# china_mp3_board.net
KiCad netlist of a schematic drawn in EAGLE
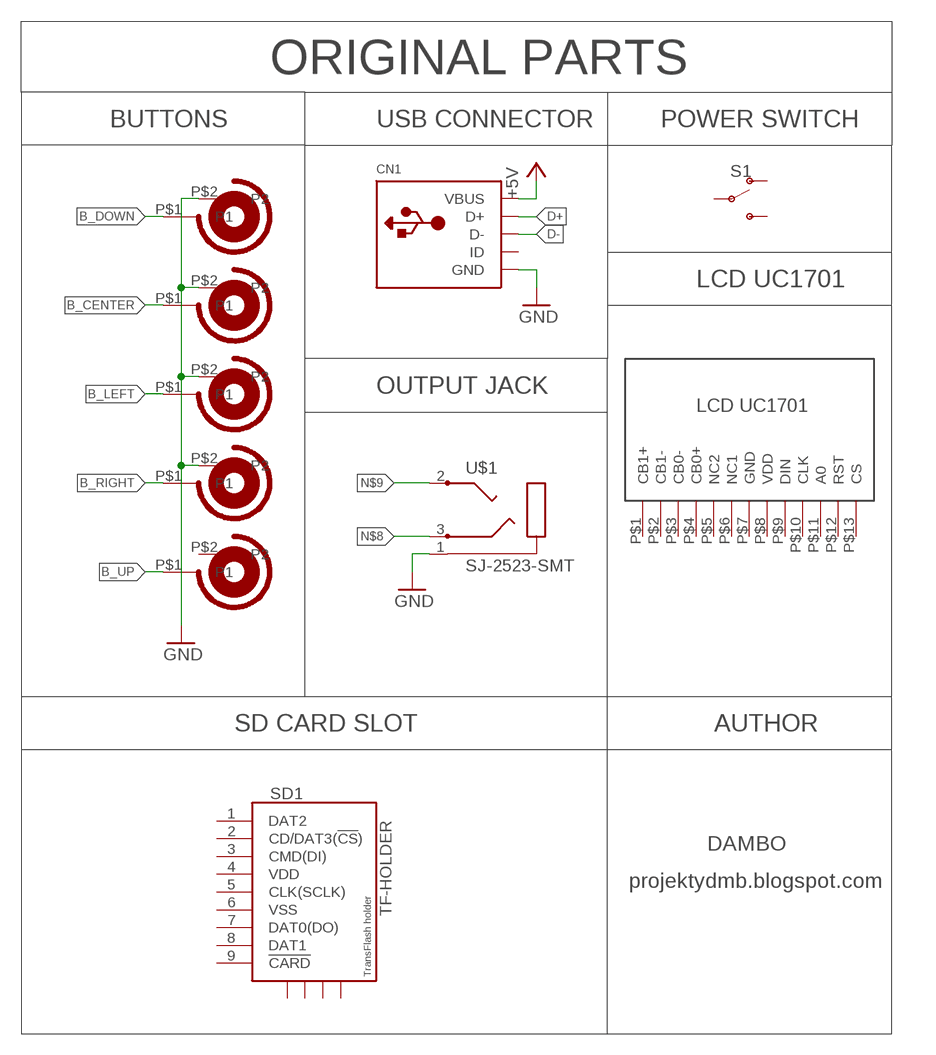
[diagram p0: schematic, sheet 1]

(export (version "E")
  (design (tool "Eeschema 10.0.6"))
  (components
    (comp (ref "CN1")
      (value "USBMINIB")
      (footprint "eagle-import:USB-MINIB")
      (libsource (lib "eagle-import") (part "USBMINIB"))
    )
    (comp (ref "S1")
      (value "SWITCH-SPDT-SMD-RIGHT-ANGLE")
      (footprint "eagle-import:SWITCH_SPST_SMD_A")
      (libsource (lib "eagle-import") (part "SWITCH-SPDT-SMD-RIGHT-ANGLE"))
    )
    (comp (ref "SD1")
      (value "TF-HOLDER")
      (footprint "eagle-import:TF-PULL")
      (libsource (lib "eagle-import") (part "TF-HOLDER"))
    )
    (comp (ref "U$1")
      (value "SJ-2523-SMT")
      (footprint "eagle-import:SJ-2523-SMT")
      (libsource (lib "eagle-import") (part "SJ-2523-SMT"))
    )
    (comp (ref "U$2")
      (value "BUTTON_TACT")
      (footprint "eagle-import:BUTTON_TACT_PACKAGE")
      (libsource (lib "eagle-import") (part "BUTTON_TACT"))
    )
    (comp (ref "U$3")
      (value "BUTTON_TACT")
      (footprint "eagle-import:BUTTON_TACT_PACKAGE")
      (libsource (lib "eagle-import") (part "BUTTON_TACT"))
    )
    (comp (ref "U$4")
      (value "BUTTON_TACT")
      (footprint "eagle-import:BUTTON_TACT_PACKAGE")
      (libsource (lib "eagle-import") (part "BUTTON_TACT"))
    )
    (comp (ref "U$5")
      (value "BUTTON_TACT")
      (footprint "eagle-import:BUTTON_TACT_PACKAGE")
      (libsource (lib "eagle-import") (part "BUTTON_TACT"))
    )
    (comp (ref "U$6")
      (value "BUTTON_TACT")
      (footprint "eagle-import:BUTTON_TACT_PACKAGE")
      (libsource (lib "eagle-import") (part "BUTTON_TACT"))
    )
    (comp (ref "U$7")
      (value "CHINA_MP3_LCD")
      (footprint "eagle-import:ONLY_PINS")
      (libsource (lib "eagle-import") (part "CHINA_MP3_LCD"))
    )
  )
  (nets
    (net (code "1") (name "+5V") (class "Default")
      (node (ref "CN1") (pin "VBUS") (pinfunction "VBUS_VBUS") (pintype "power_in"))
    )
    (net (code "2") (name "/VDD") (class "Default")
      (node (ref "SD1") (pin "4") (pinfunction "VDD_4") (pintype "power_in"))
    )
    (net (code "3") (name "/VSS") (class "Default")
      (node (ref "SD1") (pin "6") (pinfunction "VSS_6") (pintype "power_in"))
    )
    (net (code "4") (name "B_CENTER") (class "Default")
      (node (ref "U$3") (pin "P$1") (pinfunction "P1_P$1") (pintype "bidirectional"))
    )
    (net (code "5") (name "B_DOWN") (class "Default")
      (node (ref "U$2") (pin "P$1") (pinfunction "P1_P$1") (pintype "bidirectional"))
    )
    (net (code "6") (name "B_LEFT") (class "Default")
      (node (ref "U$4") (pin "P$1") (pinfunction "P1_P$1") (pintype "bidirectional"))
    )
    (net (code "7") (name "B_RIGHT") (class "Default")
      (node (ref "U$5") (pin "P$1") (pinfunction "P1_P$1") (pintype "bidirectional"))
    )
    (net (code "8") (name "B_UP") (class "Default")
      (node (ref "U$6") (pin "P$1") (pinfunction "P1_P$1") (pintype "bidirectional"))
    )
    (net (code "9") (name "D+") (class "Default")
      (node (ref "CN1") (pin "D+") (pinfunction "D+_D+") (pintype "bidirectional"))
    )
    (net (code "10") (name "D-") (class "Default")
      (node (ref "CN1") (pin "D-") (pinfunction "D-_D-") (pintype "bidirectional"))
    )
    (net (code "11") (name "GND") (class "Default")
      (node (ref "CN1") (pin "GND") (pinfunction "GND_GND") (pintype "power_in"))
      (node (ref "U$1") (pin "1") (pinfunction "EARTH_1") (pintype "passive"))
      (node (ref "U$2") (pin "P$2") (pinfunction "P2_P$2") (pintype "bidirectional"))
      (node (ref "U$3") (pin "P$2") (pinfunction "P2_P$2") (pintype "bidirectional"))
      (node (ref "U$4") (pin "P$2") (pinfunction "P2_P$2") (pintype "bidirectional"))
      (node (ref "U$5") (pin "P$2") (pinfunction "P2_P$2") (pintype "bidirectional"))
    )
    (net (code "12") (name "N$8") (class "Default")
      (node (ref "U$1") (pin "3") (pinfunction "RING_3") (pintype "passive"))
    )
    (net (code "13") (name "N$9") (class "Default")
      (node (ref "U$1") (pin "2") (pinfunction "TIP_2") (pintype "passive"))
    )
    (net (code "14") (name "unconnected-(CN1-PadID)") (class "Default")
      (node (ref "CN1") (pin "ID") (pinfunction "ID_ID") (pintype "bidirectional"))
    )
    (net (code "15") (name "unconnected-(S1-O-Pad1)") (class "Default")
      (node (ref "S1") (pin "1") (pinfunction "O_1") (pintype "passive"))
    )
    (net (code "16") (name "unconnected-(S1-P-Pad2)") (class "Default")
      (node (ref "S1") (pin "2") (pinfunction "P_2") (pintype "passive"))
    )
    (net (code "17") (name "unconnected-(S1-S-Pad3)") (class "Default")
      (node (ref "S1") (pin "3") (pinfunction "S_3") (pintype "passive"))
    )
    (net (code "18") (name "unconnected-(SD1-CD{slash}DAT3(~{CS})-Pad2)") (class "Default")
      (node (ref "SD1") (pin "2") (pinfunction "CD/DAT3(~{CS})_2") (pintype "bidirectional"))
    )
    (net (code "19") (name "unconnected-(SD1-CLK(SCLK)-Pad5)") (class "Default")
      (node (ref "SD1") (pin "5") (pinfunction "CLK(SCLK)_5") (pintype "input"))
    )
    (net (code "20") (name "unconnected-(SD1-CMD(DI)-Pad3)") (class "Default")
      (node (ref "SD1") (pin "3") (pinfunction "CMD(DI)_3") (pintype "bidirectional"))
    )
    (net (code "21") (name "unconnected-(SD1-DAT0(DO)-Pad7)") (class "Default")
      (node (ref "SD1") (pin "7") (pinfunction "DAT0(DO)_7") (pintype "bidirectional"))
    )
    (net (code "22") (name "unconnected-(SD1-DAT1-Pad8)") (class "Default")
      (node (ref "SD1") (pin "8") (pinfunction "DAT1_8") (pintype "bidirectional"))
    )
    (net (code "23") (name "unconnected-(SD1-DAT2-Pad1)") (class "Default")
      (node (ref "SD1") (pin "1") (pinfunction "DAT2_1") (pintype "bidirectional"))
    )
    (net (code "24") (name "unconnected-(SD1-PadS1)") (class "Default")
      (node (ref "SD1") (pin "S1") (pinfunction "S1_S1") (pintype "passive"))
    )
    (net (code "25") (name "unconnected-(SD1-PadS2)") (class "Default")
      (node (ref "SD1") (pin "S2") (pinfunction "S2_S2") (pintype "passive"))
    )
    (net (code "26") (name "unconnected-(SD1-PadS3)") (class "Default")
      (node (ref "SD1") (pin "S3") (pinfunction "S3_S3") (pintype "passive"))
    )
    (net (code "27") (name "unconnected-(SD1-PadS4)") (class "Default")
      (node (ref "SD1") (pin "S4") (pinfunction "S4_S4") (pintype "passive"))
    )
    (net (code "28") (name "unconnected-(SD1-~{CARD}-Pad9)") (class "Default")
      (node (ref "SD1") (pin "9") (pinfunction "~{CARD}_9") (pintype "passive"))
    )
    (net (code "29") (name "unconnected-(U$6-P2-PadP$2)") (class "Default")
      (node (ref "U$6") (pin "P$2") (pinfunction "P2_P$2") (pintype "bidirectional"))
    )
    (net (code "30") (name "unconnected-(U$7-A0-PadP$11)") (class "Default")
      (node (ref "U$7") (pin "P$11") (pinfunction "A0_P$11") (pintype "bidirectional"))
    )
    (net (code "31") (name "unconnected-(U$7-CB0+-PadP$4)") (class "Default")
      (node (ref "U$7") (pin "P$4") (pinfunction "CB0+_P$4") (pintype "bidirectional"))
    )
    (net (code "32") (name "unconnected-(U$7-CB0--PadP$3)") (class "Default")
      (node (ref "U$7") (pin "P$3") (pinfunction "CB0-_P$3") (pintype "bidirectional"))
    )
    (net (code "33") (name "unconnected-(U$7-CB1+-PadP$1)") (class "Default")
      (node (ref "U$7") (pin "P$1") (pinfunction "CB1+_P$1") (pintype "bidirectional"))
    )
    (net (code "34") (name "unconnected-(U$7-CB1--PadP$2)") (class "Default")
      (node (ref "U$7") (pin "P$2") (pinfunction "CB1-_P$2") (pintype "bidirectional"))
    )
    (net (code "35") (name "unconnected-(U$7-CLK-PadP$10)") (class "Default")
      (node (ref "U$7") (pin "P$10") (pinfunction "CLK_P$10") (pintype "bidirectional"))
    )
    (net (code "36") (name "unconnected-(U$7-CS-PadP$13)") (class "Default")
      (node (ref "U$7") (pin "P$13") (pinfunction "CS_P$13") (pintype "bidirectional"))
    )
    (net (code "37") (name "unconnected-(U$7-DIN-PadP$9)") (class "Default")
      (node (ref "U$7") (pin "P$9") (pinfunction "DIN_P$9") (pintype "bidirectional"))
    )
    (net (code "38") (name "unconnected-(U$7-GND-PadP$7)") (class "Default")
      (node (ref "U$7") (pin "P$7") (pinfunction "GND_P$7") (pintype "bidirectional"))
    )
    (net (code "39") (name "unconnected-(U$7-NC1-PadP$6)") (class "Default")
      (node (ref "U$7") (pin "P$6") (pinfunction "NC1_P$6") (pintype "bidirectional"))
    )
    (net (code "40") (name "unconnected-(U$7-NC2-PadP$5)") (class "Default")
      (node (ref "U$7") (pin "P$5") (pinfunction "NC2_P$5") (pintype "bidirectional"))
    )
    (net (code "41") (name "unconnected-(U$7-RST-PadP$12)") (class "Default")
      (node (ref "U$7") (pin "P$12") (pinfunction "RST_P$12") (pintype "bidirectional"))
    )
    (net (code "42") (name "unconnected-(U$7-VDD-PadP$8)") (class "Default")
      (node (ref "U$7") (pin "P$8") (pinfunction "VDD_P$8") (pintype "bidirectional"))
    )
  )
)
